# 0HP_OR_Gate_REV_1.net
KiCad netlist of a schematic drawn in EAGLE
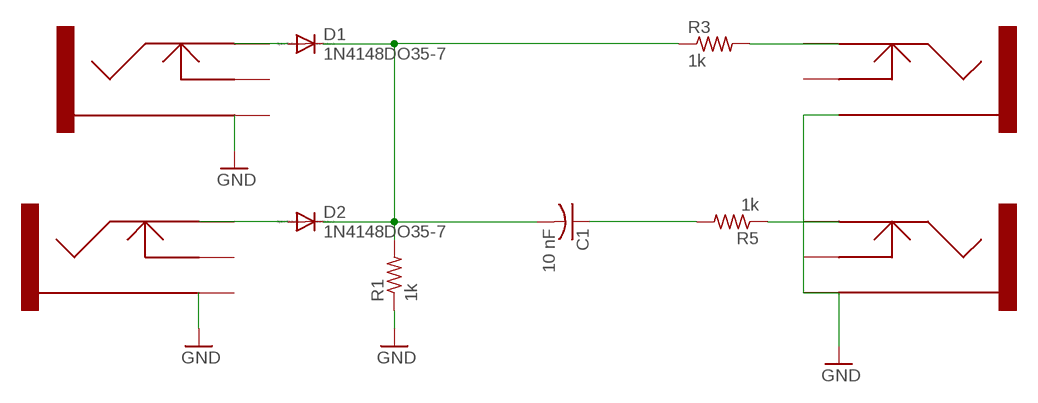
[diagram p0: schematic, sheet 1]

(export (version "E")
  (design (tool "Eeschema 10.0.6"))
  (components
    (comp (ref "C1")
      (value "10 nF")
      (footprint "eagle-import:C025-024X044")
      (libsource (lib "eagle-import") (part "C-US025-024X044"))
    )
    (comp (ref "CV1")
      (value "3.5MMJACK")
      (footprint "eagle-import:3.5MMPHONEJACK")
      (libsource (lib "eagle-import") (part "3.5MMJACK"))
    )
    (comp (ref "CV2")
      (value "3.5MMJACK")
      (footprint "eagle-import:3.5MMPHONEJACK")
      (libsource (lib "eagle-import") (part "3.5MMJACK"))
    )
    (comp (ref "D1")
      (value "1N4148DO35-7")
      (footprint "eagle-import:DO35-7")
      (libsource (lib "eagle-import") (part "1N4148DO35-7"))
    )
    (comp (ref "D2")
      (value "1N4148DO35-7")
      (footprint "eagle-import:DO35-7")
      (libsource (lib "eagle-import") (part "1N4148DO35-7"))
    )
    (comp (ref "IN")
      (value "3.5MMJACK")
      (footprint "eagle-import:3.5MMPHONEJACK")
      (libsource (lib "eagle-import") (part "3.5MMJACK"))
    )
    (comp (ref "OUT")
      (value "3.5MMJACK")
      (footprint "eagle-import:3.5MMPHONEJACK")
      (libsource (lib "eagle-import") (part "3.5MMJACK"))
    )
    (comp (ref "R1")
      (value "1k")
      (footprint "eagle-import:0207_2V")
      (libsource (lib "eagle-import") (part "R-US_0207/2V"))
    )
    (comp (ref "R3")
      (value "1k")
      (footprint "eagle-import:0207_2V")
      (libsource (lib "eagle-import") (part "R-US_0207/2V"))
    )
    (comp (ref "R5")
      (value "1k")
      (footprint "eagle-import:0207_2V")
      (libsource (lib "eagle-import") (part "R-US_0207/2V"))
    )
  )
  (nets
    (net (code "1") (name "GND") (class "Default")
      (node (ref "CV1") (pin "SLEEVE") (pinfunction "SLEEVE_SLEEVE") (pintype "bidirectional"))
      (node (ref "CV2") (pin "SLEEVE") (pinfunction "SLEEVE_SLEEVE") (pintype "bidirectional"))
      (node (ref "IN") (pin "SLEEVE") (pinfunction "SLEEVE_SLEEVE") (pintype "bidirectional"))
      (node (ref "OUT") (pin "SLEEVE") (pinfunction "SLEEVE_SLEEVE") (pintype "bidirectional"))
      (node (ref "R1") (pin "1") (pinfunction "1_1") (pintype "passive"))
    )
    (net (code "2") (name "Net-(C1-Pad1)") (class "Default")
      (node (ref "C1") (pin "1") (pinfunction "1_1") (pintype "passive"))
      (node (ref "R5") (pin "2") (pinfunction "2_2") (pintype "passive"))
    )
    (net (code "3") (name "Net-(C1-Pad2)") (class "Default")
      (node (ref "C1") (pin "2") (pinfunction "2_2") (pintype "passive"))
      (node (ref "D1") (pin "C") (pinfunction "C_C") (pintype "passive"))
      (node (ref "D2") (pin "C") (pinfunction "C_C") (pintype "passive"))
      (node (ref "R1") (pin "2") (pinfunction "2_2") (pintype "passive"))
      (node (ref "R3") (pin "1") (pinfunction "1_1") (pintype "passive"))
    )
    (net (code "4") (name "Net-(CV1-PadTIP)") (class "Default")
      (node (ref "CV1") (pin "TIP") (pinfunction "TIP_TIP") (pintype "bidirectional"))
      (node (ref "D2") (pin "A") (pinfunction "A_A") (pintype "passive"))
    )
    (net (code "5") (name "Net-(CV2-PadTIP)") (class "Default")
      (node (ref "CV2") (pin "TIP") (pinfunction "TIP_TIP") (pintype "bidirectional"))
      (node (ref "D1") (pin "A") (pinfunction "A_A") (pintype "passive"))
    )
    (net (code "6") (name "Net-(IN-PadTIP)") (class "Default")
      (node (ref "IN") (pin "TIP") (pinfunction "TIP_TIP") (pintype "bidirectional"))
      (node (ref "R5") (pin "1") (pinfunction "1_1") (pintype "passive"))
    )
    (net (code "7") (name "Net-(OUT-PadTIP)") (class "Default")
      (node (ref "OUT") (pin "TIP") (pinfunction "TIP_TIP") (pintype "bidirectional"))
      (node (ref "R3") (pin "2") (pinfunction "2_2") (pintype "passive"))
    )
    (net (code "8") (name "unconnected-(CV1-PadSWITCH)") (class "Default")
      (node (ref "CV1") (pin "SWITCH") (pinfunction "SWITCH_SWITCH") (pintype "bidirectional"))
    )
    (net (code "9") (name "unconnected-(CV2-PadSWITCH)") (class "Default")
      (node (ref "CV2") (pin "SWITCH") (pinfunction "SWITCH_SWITCH") (pintype "bidirectional"))
    )
    (net (code "10") (name "unconnected-(IN-PadSWITCH)") (class "Default")
      (node (ref "IN") (pin "SWITCH") (pinfunction "SWITCH_SWITCH") (pintype "bidirectional"))
    )
    (net (code "11") (name "unconnected-(OUT-PadSWITCH)") (class "Default")
      (node (ref "OUT") (pin "SWITCH") (pinfunction "SWITCH_SWITCH") (pintype "bidirectional"))
    )
  )
)
